# ArmazConnect_-_Rev_B4.net
KiCad netlist of a schematic drawn in EAGLE
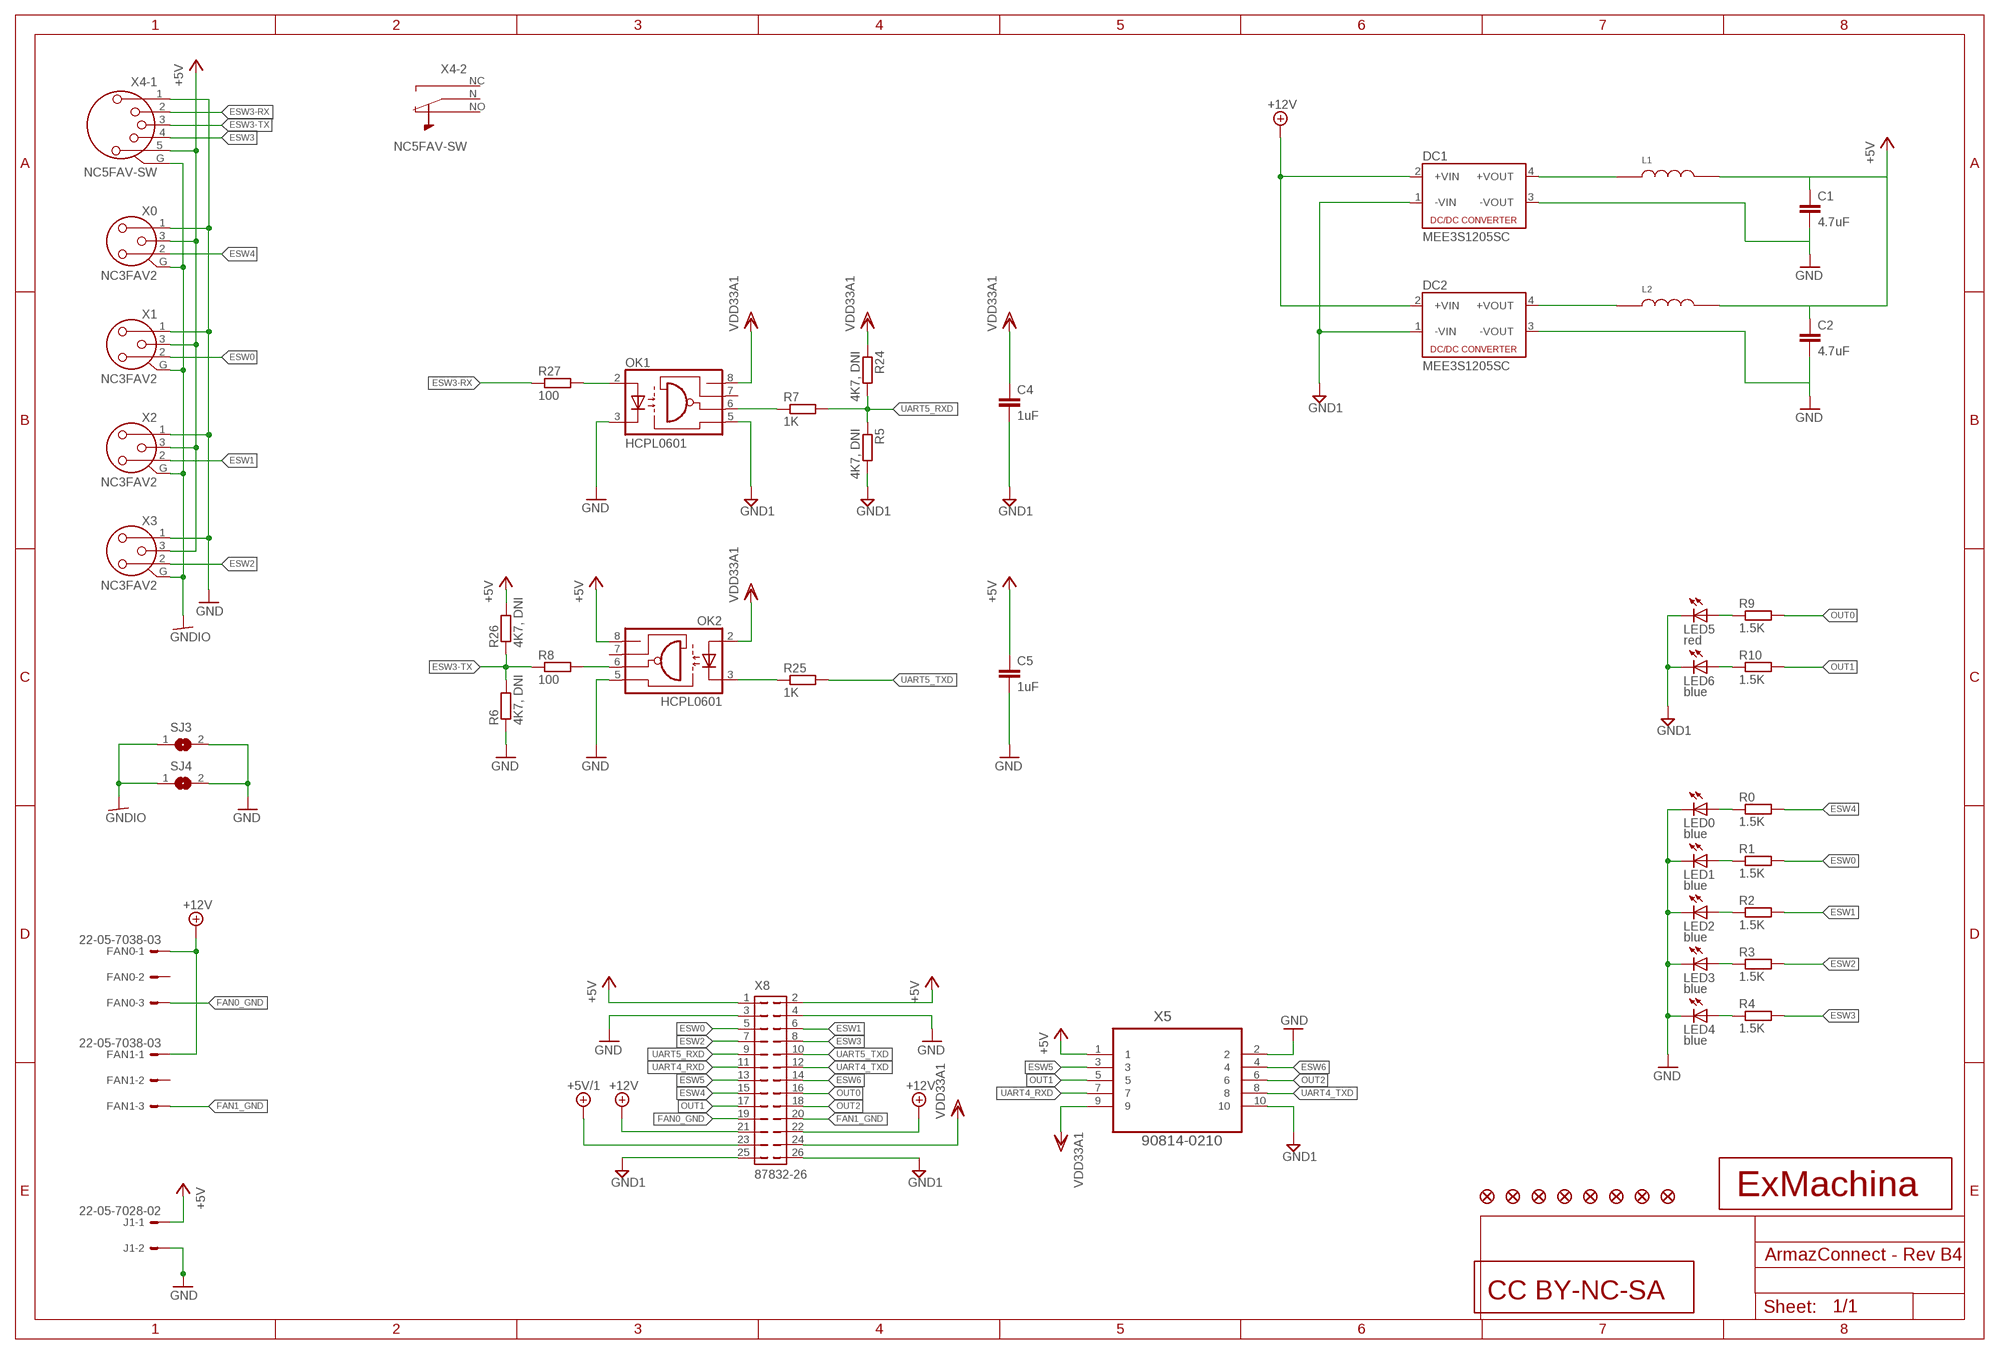
[diagram p0: schematic, sheet 1]

(export (version "E")
  (design (tool "Eeschema 10.0.6"))
  (components
    (comp (ref "C1")
      (value "4.7uF")
      (footprint "eagle-import:C0603")
      (fields (field (name "MF") "MULTICOMP") (field (name "MPN") "MC0603X475K6R3CT"))
      (libsource (lib "eagle-import") (part "C-EUC0603"))
    )
    (comp (ref "C2")
      (value "4.7uF")
      (footprint "eagle-import:C0603")
      (fields (field (name "MF") "MULTICOMP") (field (name "MPN") "MC0603X475K6R3CT"))
      (libsource (lib "eagle-import") (part "C-EUC0603"))
    )
    (comp (ref "C4")
      (value "1uF")
      (footprint "eagle-import:C0805")
      (fields (field (name "MF") "MULTICOMP") (field (name "MPN") "MC0805F105Z500CT"))
      (libsource (lib "eagle-import") (part "C-EUC0805"))
    )
    (comp (ref "C5")
      (value "1uF")
      (footprint "eagle-import:C0805")
      (fields (field (name "MF") "MULTICOMP") (field (name "MPN") "MC0805F105Z500CT"))
      (libsource (lib "eagle-import") (part "C-EUC0805"))
    )
    (comp (ref "CC1")
      (value "CC-BY-NC-SA")
      (footprint "eagle-import:CC-BY-NC-SA")
      (libsource (lib "eagle-import") (part "CC-BY-NC-SA"))
    )
    (comp (ref "DC1")
      (value "MEE3S1205SC")
      (footprint "eagle-import:MEE3")
      (fields (field (name "MF") "MURATA POWER SOLUTIONS"))
      (libsource (lib "eagle-import") (part "MEE3S1205SC"))
    )
    (comp (ref "DC2")
      (value "MEE3S1205SC")
      (footprint "eagle-import:MEE3")
      (fields (field (name "MF") "MURATA POWER SOLUTIONS"))
      (libsource (lib "eagle-import") (part "MEE3S1205SC"))
    )
    (comp (ref "FAN0")
      (value "22-05-7038-03")
      (footprint "eagle-import:7395-03")
      (fields
        (field (name "MF") "MOLEX")
        (field (name "MPN") "22-05-7038")
        (field (name "OC_FARNELL") "9731610")
      )
      (libsource (lib "eagle-import") (part "22-?-0305-7038"))
    )
    (comp (ref "FAN1")
      (value "22-05-7038-03")
      (footprint "eagle-import:7395-03")
      (fields
        (field (name "MF") "MOLEX")
        (field (name "MPN") "22-05-7038")
        (field (name "OC_FARNELL") "9731610")
      )
      (libsource (lib "eagle-import") (part "22-?-0305-7038"))
    )
    (comp (ref "FI1")
      (value "FIDUCIAL1X2")
      (footprint "eagle-import:FIDUCIAL-1X2")
      (libsource (lib "eagle-import") (part "FIDUCIAL1X2"))
    )
    (comp (ref "FI2")
      (value "FIDUCIAL1X2")
      (footprint "eagle-import:FIDUCIAL-1X2")
      (libsource (lib "eagle-import") (part "FIDUCIAL1X2"))
    )
    (comp (ref "FI3")
      (value "FIDUCIAL1X2")
      (footprint "eagle-import:FIDUCIAL-1X2")
      (libsource (lib "eagle-import") (part "FIDUCIAL1X2"))
    )
    (comp (ref "FI4")
      (value "FIDUCIAL1X2")
      (footprint "eagle-import:FIDUCIAL-1X2")
      (libsource (lib "eagle-import") (part "FIDUCIAL1X2"))
    )
    (comp (ref "FI5")
      (value "FIDUCIAL1X2")
      (footprint "eagle-import:FIDUCIAL-1X2")
      (libsource (lib "eagle-import") (part "FIDUCIAL1X2"))
    )
    (comp (ref "FI6")
      (value "FIDUCIAL1X2")
      (footprint "eagle-import:FIDUCIAL-1X2")
      (libsource (lib "eagle-import") (part "FIDUCIAL1X2"))
    )
    (comp (ref "FI7")
      (value "FIDUCIAL1X2")
      (footprint "eagle-import:FIDUCIAL-1X2")
      (libsource (lib "eagle-import") (part "FIDUCIAL1X2"))
    )
    (comp (ref "FI8")
      (value "FIDUCIAL1X2")
      (footprint "eagle-import:FIDUCIAL-1X2")
      (libsource (lib "eagle-import") (part "FIDUCIAL1X2"))
    )
    (comp (ref "J1")
      (value "22-05-7028-02")
      (footprint "eagle-import:7395-02")
      (libsource (lib "eagle-import") (part "22-?-0205-7028"))
    )
    (comp (ref "L1")
      (value "84103C")
      (footprint "eagle-import:8200")
      (fields (field (name "MF") "WURTH ELEKTRONIK") (field (name "MPN") "744045100"))
      (libsource (lib "eagle-import") (part "84103C"))
    )
    (comp (ref "L2")
      (value "84103C")
      (footprint "eagle-import:8200")
      (fields (field (name "MF") "WURTH ELEKTRONIK") (field (name "MPN") "744045100"))
      (libsource (lib "eagle-import") (part "84103C"))
    )
    (comp (ref "LED0")
      (value "blue")
      (footprint "eagle-import:CHIP-LED0603")
      (fields (field (name "MF") "MULTICOMP") (field (name "MPN") "OVS-0603"))
      (libsource (lib "eagle-import") (part "LEDCHIP-LED0603"))
    )
    (comp (ref "LED1")
      (value "blue")
      (footprint "eagle-import:CHIP-LED0603")
      (fields (field (name "MF") "MULTICOMP") (field (name "MPN") "OVS-0603"))
      (libsource (lib "eagle-import") (part "LEDCHIP-LED0603"))
    )
    (comp (ref "LED2")
      (value "blue")
      (footprint "eagle-import:CHIP-LED0603")
      (fields (field (name "MF") "MULTICOMP") (field (name "MPN") "OVS-0603"))
      (libsource (lib "eagle-import") (part "LEDCHIP-LED0603"))
    )
    (comp (ref "LED3")
      (value "blue")
      (footprint "eagle-import:CHIP-LED0603")
      (fields (field (name "MF") "MULTICOMP") (field (name "MPN") "OVS-0603"))
      (libsource (lib "eagle-import") (part "LEDCHIP-LED0603"))
    )
    (comp (ref "LED4")
      (value "blue")
      (footprint "eagle-import:CHIP-LED0603")
      (fields (field (name "MF") "MULTICOMP") (field (name "MPN") "OVS-0603"))
      (libsource (lib "eagle-import") (part "LEDCHIP-LED0603"))
    )
    (comp (ref "LED5")
      (value "red")
      (footprint "eagle-import:CHIP-LED0603")
      (fields (field (name "MF") "MULTICOMP") (field (name "MPN") "OVS-0603"))
      (libsource (lib "eagle-import") (part "LEDCHIP-LED0603"))
    )
    (comp (ref "LED6")
      (value "blue")
      (footprint "eagle-import:CHIP-LED0603")
      (fields (field (name "MF") "MULTICOMP") (field (name "MPN") "OVS-0603"))
      (libsource (lib "eagle-import") (part "LEDCHIP-LED0603"))
    )
    (comp (ref "OK1")
      (value "HCPL0601")
      (footprint "eagle-import:SOIC08")
      (fields
        (field (name "MF") "AGILENT TECHNOLOGIES")
        (field (name "MPN") "HCPL-0601-000E")
        (field (name "MF_1") "AVAGO TECHNOLOGIES")
      )
      (libsource (lib "eagle-import") (part "HCPL0601"))
    )
    (comp (ref "OK2")
      (value "HCPL0601")
      (footprint "eagle-import:SOIC08")
      (fields
        (field (name "MF") "AGILENT TECHNOLOGIES")
        (field (name "MPN") "HCPL-0601-000E")
        (field (name "MF_1") "AVAGO TECHNOLOGIES")
      )
      (libsource (lib "eagle-import") (part "HCPL0601"))
    )
    (comp (ref "R0")
      (value "1.5K")
      (footprint "eagle-import:R0603")
      (fields (field (name "MF") "MULTICOMP") (field (name "MPN") "MCMR06X1501FTL"))
      (libsource (lib "eagle-import") (part "R-EU_R0603"))
    )
    (comp (ref "R1")
      (value "1.5K")
      (footprint "eagle-import:R0603")
      (fields (field (name "MF") "MULTICOMP") (field (name "MPN") "MCMR06X1501FTL"))
      (libsource (lib "eagle-import") (part "R-EU_R0603"))
    )
    (comp (ref "R2")
      (value "1.5K")
      (footprint "eagle-import:R0603")
      (fields (field (name "MF") "MULTICOMP") (field (name "MPN") "MCMR06X1501FTL"))
      (libsource (lib "eagle-import") (part "R-EU_R0603"))
    )
    (comp (ref "R3")
      (value "1.5K")
      (footprint "eagle-import:R0603")
      (fields (field (name "MF") "MULTICOMP") (field (name "MPN") "MCMR06X1501FTL"))
      (libsource (lib "eagle-import") (part "R-EU_R0603"))
    )
    (comp (ref "R4")
      (value "1.5K")
      (footprint "eagle-import:R0603")
      (fields (field (name "MF") "MULTICOMP") (field (name "MPN") "MCMR06X1501FTL"))
      (libsource (lib "eagle-import") (part "R-EU_R0603"))
    )
    (comp (ref "R5")
      (value "4K7, DNI")
      (footprint "eagle-import:R0603")
      (fields (field (name "MF") "MULTICOMP") (field (name "MPN") "MCMR04X3301FTL"))
      (libsource (lib "eagle-import") (part "R-EU_R0603"))
    )
    (comp (ref "R6")
      (value "4K7, DNI")
      (footprint "eagle-import:R0603")
      (fields (field (name "MF") "MULTICOMP") (field (name "MPN") "MCMR04X3301FTL"))
      (libsource (lib "eagle-import") (part "R-EU_R0603"))
    )
    (comp (ref "R7")
      (value "1K")
      (footprint "eagle-import:R0603")
      (fields (field (name "MF") "MULTICOMP") (field (name "MPN") "MCMR06X3300FTL"))
      (libsource (lib "eagle-import") (part "R-EU_R0603"))
    )
    (comp (ref "R8")
      (value "100")
      (footprint "eagle-import:R0603")
      (fields (field (name "MF") "MULTICOMP") (field (name "MPN") "MCMR06X4701FTL"))
      (libsource (lib "eagle-import") (part "R-EU_R0603"))
    )
    (comp (ref "R9")
      (value "1.5K")
      (footprint "eagle-import:R0603")
      (fields (field (name "MF") "MULTICOMP") (field (name "MPN") "MCMR06X1501FTL"))
      (libsource (lib "eagle-import") (part "R-EU_R0603"))
    )
    (comp (ref "R10")
      (value "1.5K")
      (footprint "eagle-import:R0603")
      (fields (field (name "MF") "MULTICOMP") (field (name "MPN") "MCMR06X1501FTL"))
      (libsource (lib "eagle-import") (part "R-EU_R0603"))
    )
    (comp (ref "R24")
      (value "4K7, DNI")
      (footprint "eagle-import:R0603")
      (fields (field (name "MF") "MULTICOMP") (field (name "MPN") "MCMR04X3301FTL"))
      (libsource (lib "eagle-import") (part "R-EU_R0603"))
    )
    (comp (ref "R25")
      (value "1K")
      (footprint "eagle-import:R0603")
      (fields (field (name "MF") "MULTICOMP") (field (name "MPN") "MCMR06X3300FTL"))
      (libsource (lib "eagle-import") (part "R-EU_R0603"))
    )
    (comp (ref "R26")
      (value "4K7, DNI")
      (footprint "eagle-import:R0603")
      (fields (field (name "MF") "MULTICOMP") (field (name "MPN") "MCMR04X3301FTL"))
      (libsource (lib "eagle-import") (part "R-EU_R0603"))
    )
    (comp (ref "R27")
      (value "100")
      (footprint "eagle-import:R0603")
      (fields (field (name "MF") "MULTICOMP") (field (name "MPN") "MCMR06X4701FTL"))
      (libsource (lib "eagle-import") (part "R-EU_R0603"))
    )
    (comp (ref "SJ3") (value "SJ") (footprint "eagle-import:SJ") (libsource (lib "eagle-import") (part "SJ")))
    (comp (ref "SJ4") (value "SJ") (footprint "eagle-import:SJ") (libsource (lib "eagle-import") (part "SJ")))
    (comp (ref "U$1")
      (value "EXMACHINA-LOGO-NAME")
      (footprint "eagle-import:EXM-LOGO-BASELINE")
      (libsource (lib "eagle-import") (part "EXMACHINA-LOGO-NAME"))
    )
    (comp (ref "X0")
      (value "NC3FAV2")
      (footprint "eagle-import:NC3FAV2")
      (fields
        (field (name "MF") "NEUTRIK")
        (field (name "MPN") "NC3FAAV2")
        (field (name "OC_FARNELL") "1310038")
      )
      (libsource (lib "eagle-import") (part "NC3FAV2"))
    )
    (comp (ref "X1")
      (value "NC3FAV2")
      (footprint "eagle-import:NC3FAV2")
      (fields
        (field (name "MF") "NEUTRIK")
        (field (name "MPN") "NC3FAAV2")
        (field (name "OC_FARNELL") "1310038")
      )
      (libsource (lib "eagle-import") (part "NC3FAV2"))
    )
    (comp (ref "X2")
      (value "NC3FAV2")
      (footprint "eagle-import:NC3FAV2")
      (fields
        (field (name "MF") "NEUTRIK")
        (field (name "MPN") "NC3FAAV2")
        (field (name "OC_FARNELL") "1310038")
      )
      (libsource (lib "eagle-import") (part "NC3FAV2"))
    )
    (comp (ref "X3")
      (value "NC3FAV2")
      (footprint "eagle-import:NC3FAV2")
      (fields
        (field (name "MF") "NEUTRIK")
        (field (name "MPN") "NC3FAAV2")
        (field (name "OC_FARNELL") "1310038")
      )
      (libsource (lib "eagle-import") (part "NC3FAV2"))
    )
    (comp (ref "X4")
      (value "NC5FAV-SW")
      (footprint "eagle-import:NC5FAV-SW")
      (fields (field (name "MF") "NEUTRIK") (field (name "OC_FARNELL") "1310093"))
      (libsource (lib "eagle-import") (part "NC5?-SWFAV"))
    )
    (comp (ref "X5")
      (value "90814-0210")
      (footprint "eagle-import:MOLEX_90814-0210")
      (libsource (lib "eagle-import") (part "90814-0210"))
    )
    (comp (ref "X8")
      (value "87832-26")
      (footprint "eagle-import:87832-26")
      (fields
        (field (name "MF") "MOLEX")
        (field (name "MPN") "87832-2620")
        (field (name "OC_FARNELL") "2313712")
      )
      (libsource (lib "eagle-import") (part "87832-26"))
    )
  )
  (nets
    (net (code "1") (name "+5V") (class "Default")
      (node (ref "C1") (pin "1") (pinfunction "1_1") (pintype "passive"))
      (node (ref "C2") (pin "1") (pinfunction "1_1") (pintype "passive"))
      (node (ref "C5") (pin "1") (pinfunction "1_1") (pintype "passive"))
      (node (ref "J1") (pin "1") (pinfunction "S_1") (pintype "passive"))
      (node (ref "L1") (pin "2") (pinfunction "2_2") (pintype "passive"))
      (node (ref "L2") (pin "2") (pinfunction "2_2") (pintype "passive"))
      (node (ref "OK2") (pin "8") (pinfunction "VCC_8") (pintype "passive"))
      (node (ref "R26") (pin "2") (pinfunction "2_2") (pintype "passive"))
      (node (ref "X0") (pin "3") (pinfunction "3_3") (pintype "passive"))
      (node (ref "X1") (pin "3") (pinfunction "3_3") (pintype "passive"))
      (node (ref "X2") (pin "3") (pinfunction "3_3") (pintype "passive"))
      (node (ref "X3") (pin "3") (pinfunction "3_3") (pintype "passive"))
      (node (ref "X4") (pin "5") (pinfunction "5_5") (pintype "passive"))
      (node (ref "X5") (pin "1") (pinfunction "1_1") (pintype "passive"))
      (node (ref "X8") (pin "1") (pinfunction "1_1") (pintype "passive"))
      (node (ref "X8") (pin "2") (pinfunction "2_2") (pintype "passive"))
    )
    (net (code "2") (name "+5V{slash}1") (class "Default")
      (node (ref "X8") (pin "23") (pinfunction "23_23") (pintype "passive"))
    )
    (net (code "3") (name "+12V") (class "Default")
      (node (ref "DC1") (pin "2") (pinfunction "+VIN_2") (pintype "passive"))
      (node (ref "DC2") (pin "2") (pinfunction "+VIN_2") (pintype "passive"))
      (node (ref "FAN0") (pin "1") (pinfunction "S_1") (pintype "passive"))
      (node (ref "FAN1") (pin "1") (pinfunction "S_1") (pintype "passive"))
      (node (ref "X8") (pin "21") (pinfunction "21_21") (pintype "passive"))
      (node (ref "X8") (pin "22") (pinfunction "22_22") (pintype "passive"))
    )
    (net (code "4") (name "ESW0") (class "Default")
      (node (ref "R1") (pin "2") (pinfunction "2_2") (pintype "passive"))
      (node (ref "X1") (pin "2") (pinfunction "2_2") (pintype "passive"))
      (node (ref "X8") (pin "5") (pinfunction "5_5") (pintype "passive"))
    )
    (net (code "5") (name "ESW1") (class "Default")
      (node (ref "R2") (pin "2") (pinfunction "2_2") (pintype "passive"))
      (node (ref "X2") (pin "2") (pinfunction "2_2") (pintype "passive"))
      (node (ref "X8") (pin "6") (pinfunction "6_6") (pintype "passive"))
    )
    (net (code "6") (name "ESW2") (class "Default")
      (node (ref "R3") (pin "2") (pinfunction "2_2") (pintype "passive"))
      (node (ref "X3") (pin "2") (pinfunction "2_2") (pintype "passive"))
      (node (ref "X8") (pin "7") (pinfunction "7_7") (pintype "passive"))
    )
    (net (code "7") (name "ESW3") (class "Default")
      (node (ref "R4") (pin "2") (pinfunction "2_2") (pintype "passive"))
      (node (ref "X4") (pin "4") (pinfunction "4_4") (pintype "passive"))
      (node (ref "X8") (pin "8") (pinfunction "8_8") (pintype "passive"))
    )
    (net (code "8") (name "ESW3-RX") (class "Default")
      (node (ref "R27") (pin "1") (pinfunction "1_1") (pintype "passive"))
      (node (ref "X4") (pin "2") (pinfunction "2_2") (pintype "passive"))
    )
    (net (code "9") (name "ESW3-TX") (class "Default")
      (node (ref "R26") (pin "1") (pinfunction "1_1") (pintype "passive"))
      (node (ref "R6") (pin "2") (pinfunction "2_2") (pintype "passive"))
      (node (ref "R8") (pin "1") (pinfunction "1_1") (pintype "passive"))
      (node (ref "X4") (pin "3") (pinfunction "3_3") (pintype "passive"))
    )
    (net (code "10") (name "ESW4") (class "Default")
      (node (ref "R0") (pin "2") (pinfunction "2_2") (pintype "passive"))
      (node (ref "X0") (pin "2") (pinfunction "2_2") (pintype "passive"))
      (node (ref "X8") (pin "15") (pinfunction "15_15") (pintype "passive"))
    )
    (net (code "11") (name "ESW5") (class "Default")
      (node (ref "X5") (pin "3") (pinfunction "3_3") (pintype "passive"))
      (node (ref "X8") (pin "13") (pinfunction "13_13") (pintype "passive"))
    )
    (net (code "12") (name "ESW6") (class "Default")
      (node (ref "X5") (pin "4") (pinfunction "4_4") (pintype "passive"))
      (node (ref "X8") (pin "14") (pinfunction "14_14") (pintype "passive"))
    )
    (net (code "13") (name "FAN0_GND") (class "Default")
      (node (ref "FAN0") (pin "3") (pinfunction "S_3") (pintype "passive"))
      (node (ref "X8") (pin "19") (pinfunction "19_19") (pintype "passive"))
    )
    (net (code "14") (name "FAN1_GND") (class "Default")
      (node (ref "FAN1") (pin "3") (pinfunction "S_3") (pintype "passive"))
      (node (ref "X8") (pin "20") (pinfunction "20_20") (pintype "passive"))
    )
    (net (code "15") (name "GND") (class "Default")
      (node (ref "C1") (pin "2") (pinfunction "2_2") (pintype "passive"))
      (node (ref "C2") (pin "2") (pinfunction "2_2") (pintype "passive"))
      (node (ref "C5") (pin "2") (pinfunction "2_2") (pintype "passive"))
      (node (ref "DC1") (pin "3") (pinfunction "-VOUT_3") (pintype "passive"))
      (node (ref "DC2") (pin "3") (pinfunction "-VOUT_3") (pintype "passive"))
      (node (ref "J1") (pin "2") (pinfunction "S_2") (pintype "passive"))
      (node (ref "LED0") (pin "C") (pinfunction "C_C") (pintype "passive"))
      (node (ref "LED1") (pin "C") (pinfunction "C_C") (pintype "passive"))
      (node (ref "LED2") (pin "C") (pinfunction "C_C") (pintype "passive"))
      (node (ref "LED3") (pin "C") (pinfunction "C_C") (pintype "passive"))
      (node (ref "LED4") (pin "C") (pinfunction "C_C") (pintype "passive"))
      (node (ref "OK1") (pin "3") (pinfunction "C_3") (pintype "passive"))
      (node (ref "OK2") (pin "5") (pinfunction "GND_5") (pintype "passive"))
      (node (ref "R6") (pin "1") (pinfunction "1_1") (pintype "passive"))
      (node (ref "SJ3") (pin "2") (pinfunction "2_2") (pintype "passive"))
      (node (ref "SJ4") (pin "2") (pinfunction "2_2") (pintype "passive"))
      (node (ref "X0") (pin "1") (pinfunction "1_1") (pintype "passive"))
      (node (ref "X1") (pin "1") (pinfunction "1_1") (pintype "passive"))
      (node (ref "X2") (pin "1") (pinfunction "1_1") (pintype "passive"))
      (node (ref "X3") (pin "1") (pinfunction "1_1") (pintype "passive"))
      (node (ref "X4") (pin "1") (pinfunction "1_1") (pintype "passive"))
      (node (ref "X5") (pin "2") (pinfunction "2_2") (pintype "passive"))
      (node (ref "X8") (pin "3") (pinfunction "3_3") (pintype "passive"))
      (node (ref "X8") (pin "4") (pinfunction "4_4") (pintype "passive"))
    )
    (net (code "16") (name "GND1") (class "Default")
      (node (ref "C4") (pin "2") (pinfunction "2_2") (pintype "passive"))
      (node (ref "DC1") (pin "1") (pinfunction "-VIN_1") (pintype "passive"))
      (node (ref "DC2") (pin "1") (pinfunction "-VIN_1") (pintype "passive"))
      (node (ref "LED5") (pin "C") (pinfunction "C_C") (pintype "passive"))
      (node (ref "LED6") (pin "C") (pinfunction "C_C") (pintype "passive"))
      (node (ref "OK1") (pin "5") (pinfunction "GND_5") (pintype "passive"))
      (node (ref "R5") (pin "2") (pinfunction "2_2") (pintype "passive"))
      (node (ref "X5") (pin "10") (pinfunction "10_10") (pintype "passive"))
      (node (ref "X8") (pin "25") (pinfunction "25_25") (pintype "passive"))
      (node (ref "X8") (pin "26") (pinfunction "26_26") (pintype "passive"))
    )
    (net (code "17") (name "GNDIO") (class "Default")
      (node (ref "SJ3") (pin "1") (pinfunction "1_1") (pintype "passive"))
      (node (ref "SJ4") (pin "1") (pinfunction "1_1") (pintype "passive"))
      (node (ref "X0") (pin "G") (pinfunction "G_G") (pintype "passive"))
      (node (ref "X1") (pin "G") (pinfunction "G_G") (pintype "passive"))
      (node (ref "X2") (pin "G") (pinfunction "G_G") (pintype "passive"))
      (node (ref "X3") (pin "G") (pinfunction "G_G") (pintype "passive"))
      (node (ref "X4") (pin "G") (pinfunction "G_G") (pintype "passive"))
    )
    (net (code "18") (name "Net-(DC1-+VOUT)") (class "Default")
      (node (ref "DC1") (pin "4") (pinfunction "+VOUT_4") (pintype "passive"))
      (node (ref "L1") (pin "1") (pinfunction "1_1") (pintype "passive"))
    )
    (net (code "19") (name "Net-(DC2-+VOUT)") (class "Default")
      (node (ref "DC2") (pin "4") (pinfunction "+VOUT_4") (pintype "passive"))
      (node (ref "L2") (pin "1") (pinfunction "1_1") (pintype "passive"))
    )
    (net (code "20") (name "Net-(LED0-PadA)") (class "Default")
      (node (ref "LED0") (pin "A") (pinfunction "A_A") (pintype "passive"))
      (node (ref "R0") (pin "1") (pinfunction "1_1") (pintype "passive"))
    )
    (net (code "21") (name "Net-(LED1-PadA)") (class "Default")
      (node (ref "LED1") (pin "A") (pinfunction "A_A") (pintype "passive"))
      (node (ref "R1") (pin "1") (pinfunction "1_1") (pintype "passive"))
    )
    (net (code "22") (name "Net-(LED2-PadA)") (class "Default")
      (node (ref "LED2") (pin "A") (pinfunction "A_A") (pintype "passive"))
      (node (ref "R2") (pin "1") (pinfunction "1_1") (pintype "passive"))
    )
    (net (code "23") (name "Net-(LED3-PadA)") (class "Default")
      (node (ref "LED3") (pin "A") (pinfunction "A_A") (pintype "passive"))
      (node (ref "R3") (pin "1") (pinfunction "1_1") (pintype "passive"))
    )
    (net (code "24") (name "Net-(LED4-PadA)") (class "Default")
      (node (ref "LED4") (pin "A") (pinfunction "A_A") (pintype "passive"))
      (node (ref "R4") (pin "1") (pinfunction "1_1") (pintype "passive"))
    )
    (net (code "25") (name "Net-(LED5-PadA)") (class "Default")
      (node (ref "LED5") (pin "A") (pinfunction "A_A") (pintype "passive"))
      (node (ref "R9") (pin "1") (pinfunction "1_1") (pintype "passive"))
    )
    (net (code "26") (name "Net-(LED6-PadA)") (class "Default")
      (node (ref "LED6") (pin "A") (pinfunction "A_A") (pintype "passive"))
      (node (ref "R10") (pin "1") (pinfunction "1_1") (pintype "passive"))
    )
    (net (code "27") (name "Net-(OK1-A)") (class "Default")
      (node (ref "OK1") (pin "2") (pinfunction "A_2") (pintype "passive"))
      (node (ref "R27") (pin "2") (pinfunction "2_2") (pintype "passive"))
    )
    (net (code "28") (name "Net-(OK1-VO)") (class "Default")
      (node (ref "OK1") (pin "6") (pinfunction "VO_6") (pintype "passive"))
      (node (ref "R7") (pin "1") (pinfunction "1_1") (pintype "passive"))
    )
    (net (code "29") (name "Net-(OK2-C)") (class "Default")
      (node (ref "OK2") (pin "3") (pinfunction "C_3") (pintype "passive"))
      (node (ref "R25") (pin "1") (pinfunction "1_1") (pintype "passive"))
    )
    (net (code "30") (name "Net-(OK2-VO)") (class "Default")
      (node (ref "OK2") (pin "6") (pinfunction "VO_6") (pintype "passive"))
      (node (ref "R8") (pin "2") (pinfunction "2_2") (pintype "passive"))
    )
    (net (code "31") (name "OUT0") (class "Default")
      (node (ref "R9") (pin "2") (pinfunction "2_2") (pintype "passive"))
      (node (ref "X8") (pin "16") (pinfunction "16_16") (pintype "passive"))
    )
    (net (code "32") (name "OUT1") (class "Default")
      (node (ref "R10") (pin "2") (pinfunction "2_2") (pintype "passive"))
      (node (ref "X5") (pin "5") (pinfunction "5_5") (pintype "passive"))
      (node (ref "X8") (pin "17") (pinfunction "17_17") (pintype "passive"))
    )
    (net (code "33") (name "OUT2") (class "Default")
      (node (ref "X5") (pin "6") (pinfunction "6_6") (pintype "passive"))
      (node (ref "X8") (pin "18") (pinfunction "18_18") (pintype "passive"))
    )
    (net (code "34") (name "UART4_RXD") (class "Default")
      (node (ref "X5") (pin "7") (pinfunction "7_7") (pintype "passive"))
      (node (ref "X8") (pin "11") (pinfunction "11_11") (pintype "passive"))
    )
    (net (code "35") (name "UART4_TXD") (class "Default")
      (node (ref "X5") (pin "8") (pinfunction "8_8") (pintype "passive"))
      (node (ref "X8") (pin "12") (pinfunction "12_12") (pintype "passive"))
    )
    (net (code "36") (name "UART5_RXD") (class "Default")
      (node (ref "R24") (pin "2") (pinfunction "2_2") (pintype "passive"))
      (node (ref "R5") (pin "1") (pinfunction "1_1") (pintype "passive"))
      (node (ref "R7") (pin "2") (pinfunction "2_2") (pintype "passive"))
      (node (ref "X8") (pin "9") (pinfunction "9_9") (pintype "passive"))
    )
    (net (code "37") (name "UART5_TXD") (class "Default")
      (node (ref "R25") (pin "2") (pinfunction "2_2") (pintype "passive"))
      (node (ref "X8") (pin "10") (pinfunction "10_10") (pintype "passive"))
    )
    (net (code "38") (name "VDD33A1") (class "Default")
      (node (ref "C4") (pin "1") (pinfunction "1_1") (pintype "passive"))
      (node (ref "OK1") (pin "8") (pinfunction "VCC_8") (pintype "passive"))
      (node (ref "OK2") (pin "2") (pinfunction "A_2") (pintype "passive"))
      (node (ref "R24") (pin "1") (pinfunction "1_1") (pintype "passive"))
      (node (ref "X5") (pin "9") (pinfunction "9_9") (pintype "passive"))
      (node (ref "X8") (pin "24") (pinfunction "24_24") (pintype "passive"))
    )
    (net (code "39") (name "unconnected-(FAN0B-S-Pad2)") (class "Default")
      (node (ref "FAN0") (pin "2") (pinfunction "S_2") (pintype "passive"))
    )
    (net (code "40") (name "unconnected-(FAN1B-S-Pad2)") (class "Default")
      (node (ref "FAN1") (pin "2") (pinfunction "S_2") (pintype "passive"))
    )
    (net (code "41") (name "unconnected-(OK1-VE-Pad7)") (class "Default")
      (node (ref "OK1") (pin "7") (pinfunction "VE_7") (pintype "passive"))
    )
    (net (code "42") (name "unconnected-(OK2-VE-Pad7)") (class "Default")
      (node (ref "OK2") (pin "7") (pinfunction "VE_7") (pintype "passive"))
    )
    (net (code "43") (name "unconnected-(X4-PadN)") (class "Default")
      (node (ref "X4") (pin "N") (pinfunction "N_N") (pintype "passive"))
    )
    (net (code "44") (name "unconnected-(X4-PadNC)") (class "Default")
      (node (ref "X4") (pin "NC") (pinfunction "NC_NC") (pintype "passive"))
    )
    (net (code "45") (name "unconnected-(X4-PadNO)") (class "Default")
      (node (ref "X4") (pin "NO") (pinfunction "NO_NO") (pintype "passive"))
    )
  )
)
